# IRGenerator.net
KiCad netlist of a schematic drawn in Altium Designer
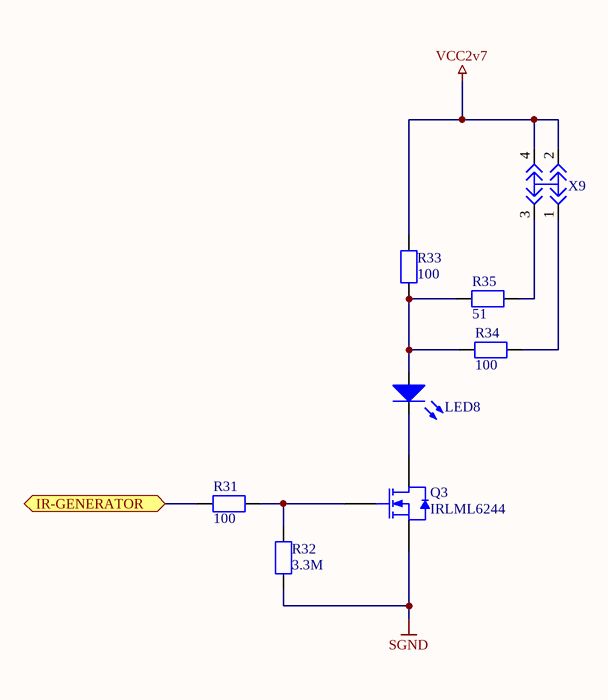
[diagram p0: IRGenerator.SchDoc]

(export (version "E")
  (design (tool "Eeschema 10.0.6"))
  (components
    (comp (ref "LED8")
      (value "L53F3C")
      (footprint "LED-5-SHORT-LEGS")
      (description "IR LED")
      (libsource (lib "MCounter_Common") (part "L53F3C"))
    )
    (comp (ref "Q3")
      (value "IRLML6244")
      (footprint "SOT23_N")
      (description "N-Channel Power MOSFET")
      (libsource (lib "MCounter_Common") (part "IRLML6244"))
    )
    (comp (ref "R31")
      (value "100")
      (footprint "R0805")
      (description "R-100-5%")
      (fields (field (name "Comment") "R100-5%"))
      (libsource (lib "") (part "R100-5%_1"))
    )
    (comp (ref "R32")
      (value "3.3M")
      (footprint "R0805")
      (description "R3.3M-5%")
      (libsource (lib "MCounter_Common") (part "R3.3M-5%"))
    )
    (comp (ref "R33")
      (value "100")
      (footprint "R1206")
      (description "R-100-5%")
      (fields (field (name "Comment") "R100-5%"))
      (libsource (lib "MCounter_Common") (part "R100-5%"))
    )
    (comp (ref "R34")
      (value "100")
      (footprint "R1206")
      (description "R-100-5%")
      (fields (field (name "Comment") "R100-5%"))
      (libsource (lib "") (part "R100-5%_2"))
    )
    (comp (ref "R35")
      (value "51")
      (footprint "R1206")
      (description "R-51-5%")
      (fields (field (name "Comment") "R51-5%"))
      (libsource (lib "MCounter_Common") (part "R51-5%"))
    )
    (comp (ref "X9")
      (value "JUMPER-PLD-POWER-0-1-2")
      (footprint "PLD-POWER-1-2-3")
      (libsource (lib "MCounter_Common") (part "JUMPER-PLD-POWER-0-1-2"))
    )
  )
  (nets
    (net (code "1") (name "/IR-GENERATOR") (class "Default")
      (node (ref "R31") (pin "1") (pinfunction "1_1") (pintype "passive"))
    )
    (net (code "2") (name "Net-(LED8-A)") (class "Default")
      (node (ref "LED8") (pin "1") (pinfunction "A_1") (pintype "passive"))
      (node (ref "R33") (pin "1") (pinfunction "1_1") (pintype "passive"))
      (node (ref "R34") (pin "2") (pinfunction "2_2") (pintype "passive"))
      (node (ref "R35") (pin "2") (pinfunction "2_2") (pintype "passive"))
    )
    (net (code "3") (name "Net-(LED8-K)") (class "Default")
      (node (ref "LED8") (pin "2") (pinfunction "K_2") (pintype "passive"))
      (node (ref "Q3") (pin "3") (pinfunction "D_3") (pintype "passive"))
    )
    (net (code "4") (name "Net-(Q3-G)") (class "Default")
      (node (ref "Q3") (pin "1") (pinfunction "G_1") (pintype "passive"))
      (node (ref "R31") (pin "2") (pinfunction "2_2") (pintype "passive"))
      (node (ref "R32") (pin "1") (pinfunction "1_1") (pintype "passive"))
    )
    (net (code "5") (name "Net-(R34-Pad1)") (class "Default")
      (node (ref "R34") (pin "1") (pinfunction "1_1") (pintype "passive"))
      (node (ref "X9") (pin "1") (pinfunction "1_1") (pintype "passive"))
    )
    (net (code "6") (name "Net-(R35-Pad1)") (class "Default")
      (node (ref "R35") (pin "1") (pinfunction "1_1") (pintype "passive"))
      (node (ref "X9") (pin "3") (pinfunction "3_3") (pintype "passive"))
    )
    (net (code "7") (name "SGND") (class "Default")
      (node (ref "Q3") (pin "2") (pinfunction "S_2") (pintype "passive"))
      (node (ref "R32") (pin "2") (pinfunction "2_2") (pintype "passive"))
    )
    (net (code "8") (name "VCC2v7") (class "Default")
      (node (ref "R33") (pin "2") (pinfunction "2_2") (pintype "passive"))
      (node (ref "X9") (pin "2") (pinfunction "2_2") (pintype "passive"))
      (node (ref "X9") (pin "4") (pinfunction "4_4") (pintype "passive"))
    )
  )
)
